# Power.net
KiCad netlist of a schematic drawn in Altium Designer
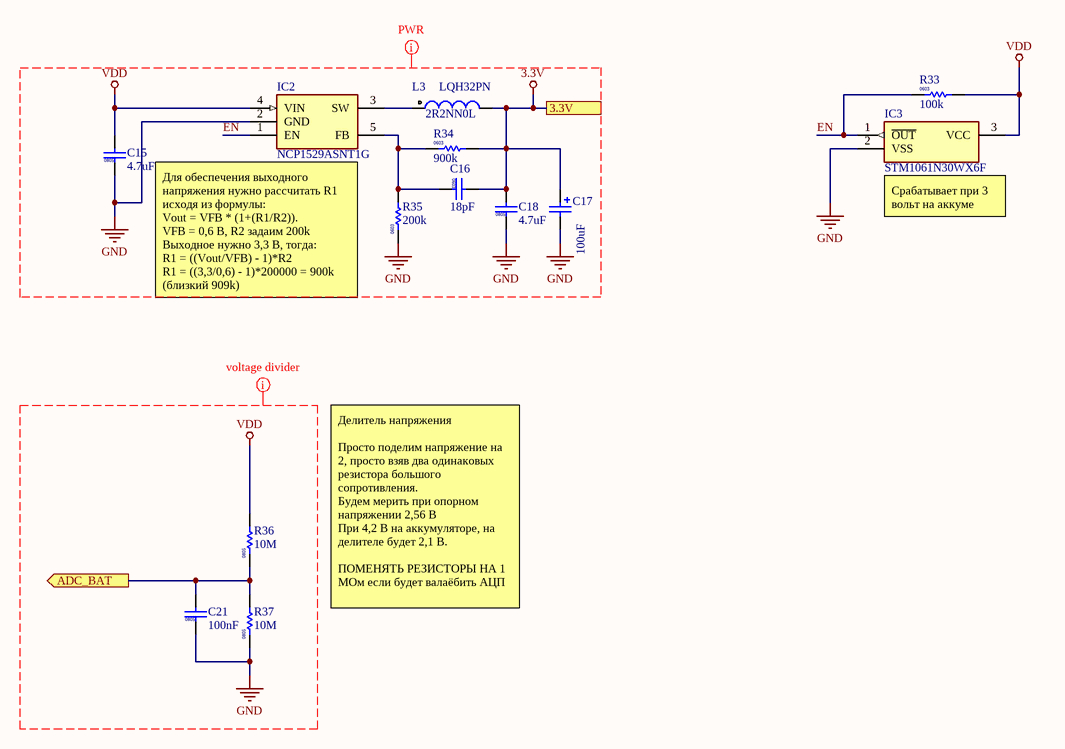
[diagram p0: Power.SchDoc]

(export (version "E")
  (design (tool "Eeschema 10.0.6"))
  (components
    (comp (ref "C15")
      (value "4.7uF")
      (footprint "CAPC2012-0805M")
      (description "Capacitor 0805")
      (fields (field (name "Comment") "CAPC_0805"))
      (libsource (lib "Passive") (part "CAPC_0805"))
    )
    (comp (ref "C16")
      (value "18pF")
      (footprint "CAPC1608-0603M")
      (description "Capacitor 0603")
      (fields (field (name "Comment") "CAPC_0603"))
      (libsource (lib "Passive") (part "CAPC_0603"))
    )
    (comp (ref "C17")
      (value "100uF")
      (footprint "ECAPC_0505")
      (description "Electrolytic Capacitor SMD 0505")
      (fields (field (name "Comment") "ECAPC_0505") (field (name "PUBLISHER") "Altium Limited"))
      (libsource (lib "Passive") (part "ECAPC_0505"))
    )
    (comp (ref "C18")
      (value "4.7uF")
      (footprint "CAPC2012-0805M")
      (description "Capacitor 0805")
      (fields (field (name "Comment") "CAPC_0805"))
      (libsource (lib "Passive") (part "CAPC_0805"))
    )
    (comp (ref "C21")
      (value "100nF")
      (footprint "CAPC2012-0805M")
      (description "Capacitor 0805")
      (fields (field (name "Comment") "CAPC_0805"))
      (libsource (lib "Passive") (part "CAPC_0805"))
    )
    (comp (ref "IC2")
      (value "NCP1529ASNT1G")
      (footprint "SOT95P275X110-5N")
      (description "Integrated Circuit")
      (fields
        (field (name "MOUSER PART NUMBER") "863-NCP1529ASNT1G")
        (field (name "RS PART NUMBER") "8023161P")
      )
      (libsource (lib "Bogdanov") (part "NCP1529ASNT1G"))
    )
    (comp (ref "IC3")
      (value "STM1061N30WX6F")
      (footprint "Bogdanov:SOT103P237X112-3N")
      (description "Integrated Circuit")
      (fields
        (field (name "MANUFACTURER_PART_NUMBER") "STM1061N34WX6F")
        (field (name "MOUSER PART NUMBER") "511-STM1061N34WX6F")
      )
      (libsource (lib "Bogdanov") (part "STM1061N34WX6F"))
    )
    (comp (ref "L3")
      (value "LQH32PN")
      (footprint "LQH32PN_M")
      (description "LQH32PN Murata inductor")
      (fields (field (name "ALTIUM_VALUE") "2R2NN0L") (field (name "PUBLISHER") "Altium Limited"))
      (libsource (lib "Passive") (part "LQH32PN"))
    )
    (comp (ref "R33")
      (value "100k")
      (footprint "RESC1608-0603M")
      (description "Resistor 0603")
      (fields (field (name "Comment") "RESC_0603"))
      (libsource (lib "Passive") (part "RESC_0603"))
    )
    (comp (ref "R34")
      (value "900k")
      (footprint "RESC1608-0603M")
      (description "Resistor 0603")
      (fields (field (name "Comment") "RESC_0603"))
      (libsource (lib "Passive") (part "RESC_0603"))
    )
    (comp (ref "R35")
      (value "200k")
      (footprint "RESC1608-0603M")
      (description "Resistor 0603")
      (fields (field (name "Comment") "RESC_0603"))
      (libsource (lib "Passive") (part "RESC_0603"))
    )
    (comp (ref "R36")
      (value "10M")
      (footprint "RESC2012-0805M")
      (description "Resistor 0805")
      (fields (field (name "Comment") "RESC_0805"))
      (libsource (lib "Passive") (part "RESC_0805"))
    )
    (comp (ref "R37")
      (value "10M")
      (footprint "RESC2012-0805M")
      (description "Resistor 0805")
      (fields (field (name "Comment") "RESC_0805"))
      (libsource (lib "Passive") (part "RESC_0805"))
    )
  )
  (nets
    (net (code "1") (name "/ADC_BAT") (class "Default")
      (node (ref "C21") (pin "2") (pinfunction "2_2") (pintype "passive"))
      (node (ref "R36") (pin "1") (pinfunction "1_1") (pintype "passive"))
      (node (ref "R37") (pin "2") (pinfunction "2_2") (pintype "passive"))
    )
    (net (code "2") (name "/EN") (class "Default")
      (node (ref "IC2") (pin "1") (pinfunction "EN_1") (pintype "passive"))
      (node (ref "IC3") (pin "1") (pinfunction "~{OUT}_1") (pintype "output"))
      (node (ref "R33") (pin "1") (pinfunction "1_1") (pintype "passive"))
    )
    (net (code "3") (name "3.3V") (class "Default")
      (node (ref "C16") (pin "2") (pinfunction "2_2") (pintype "passive"))
      (node (ref "C17") (pin "1") (pinfunction "1_1") (pintype "passive"))
      (node (ref "C18") (pin "2") (pinfunction "2_2") (pintype "passive"))
      (node (ref "L3") (pin "2") (pinfunction "2_2") (pintype "passive"))
      (node (ref "R34") (pin "2") (pinfunction "2_2") (pintype "passive"))
    )
    (net (code "4") (name "GND") (class "Default")
      (node (ref "C15") (pin "1") (pinfunction "1_1") (pintype "passive"))
      (node (ref "C17") (pin "2") (pinfunction "2_2") (pintype "passive"))
      (node (ref "C18") (pin "1") (pinfunction "1_1") (pintype "passive"))
      (node (ref "C21") (pin "1") (pinfunction "1_1") (pintype "passive"))
      (node (ref "IC2") (pin "2") (pinfunction "GND_2") (pintype "power_in"))
      (node (ref "IC3") (pin "2") (pinfunction "VSS_2") (pintype "power_in"))
      (node (ref "R35") (pin "1") (pinfunction "1_1") (pintype "passive"))
      (node (ref "R37") (pin "1") (pinfunction "1_1") (pintype "passive"))
    )
    (net (code "5") (name "Net-(IC2-FB)") (class "Default")
      (node (ref "C16") (pin "1") (pinfunction "1_1") (pintype "passive"))
      (node (ref "IC2") (pin "5") (pinfunction "FB_5") (pintype "passive"))
      (node (ref "R34") (pin "1") (pinfunction "1_1") (pintype "passive"))
      (node (ref "R35") (pin "2") (pinfunction "2_2") (pintype "passive"))
    )
    (net (code "6") (name "Net-(IC2-SW)") (class "Default")
      (node (ref "IC2") (pin "3") (pinfunction "SW_3") (pintype "passive"))
      (node (ref "L3") (pin "1") (pinfunction "1_1") (pintype "passive"))
    )
    (net (code "7") (name "VDD") (class "Default")
      (node (ref "C15") (pin "2") (pinfunction "2_2") (pintype "passive"))
      (node (ref "IC2") (pin "4") (pinfunction "VIN_4") (pintype "input"))
      (node (ref "IC3") (pin "3") (pinfunction "VCC_3") (pintype "power_in"))
      (node (ref "R33") (pin "2") (pinfunction "2_2") (pintype "passive"))
      (node (ref "R36") (pin "2") (pinfunction "2_2") (pintype "passive"))
    )
  )
)
